# Power.net
KiCad netlist of a schematic drawn in Altium Designer
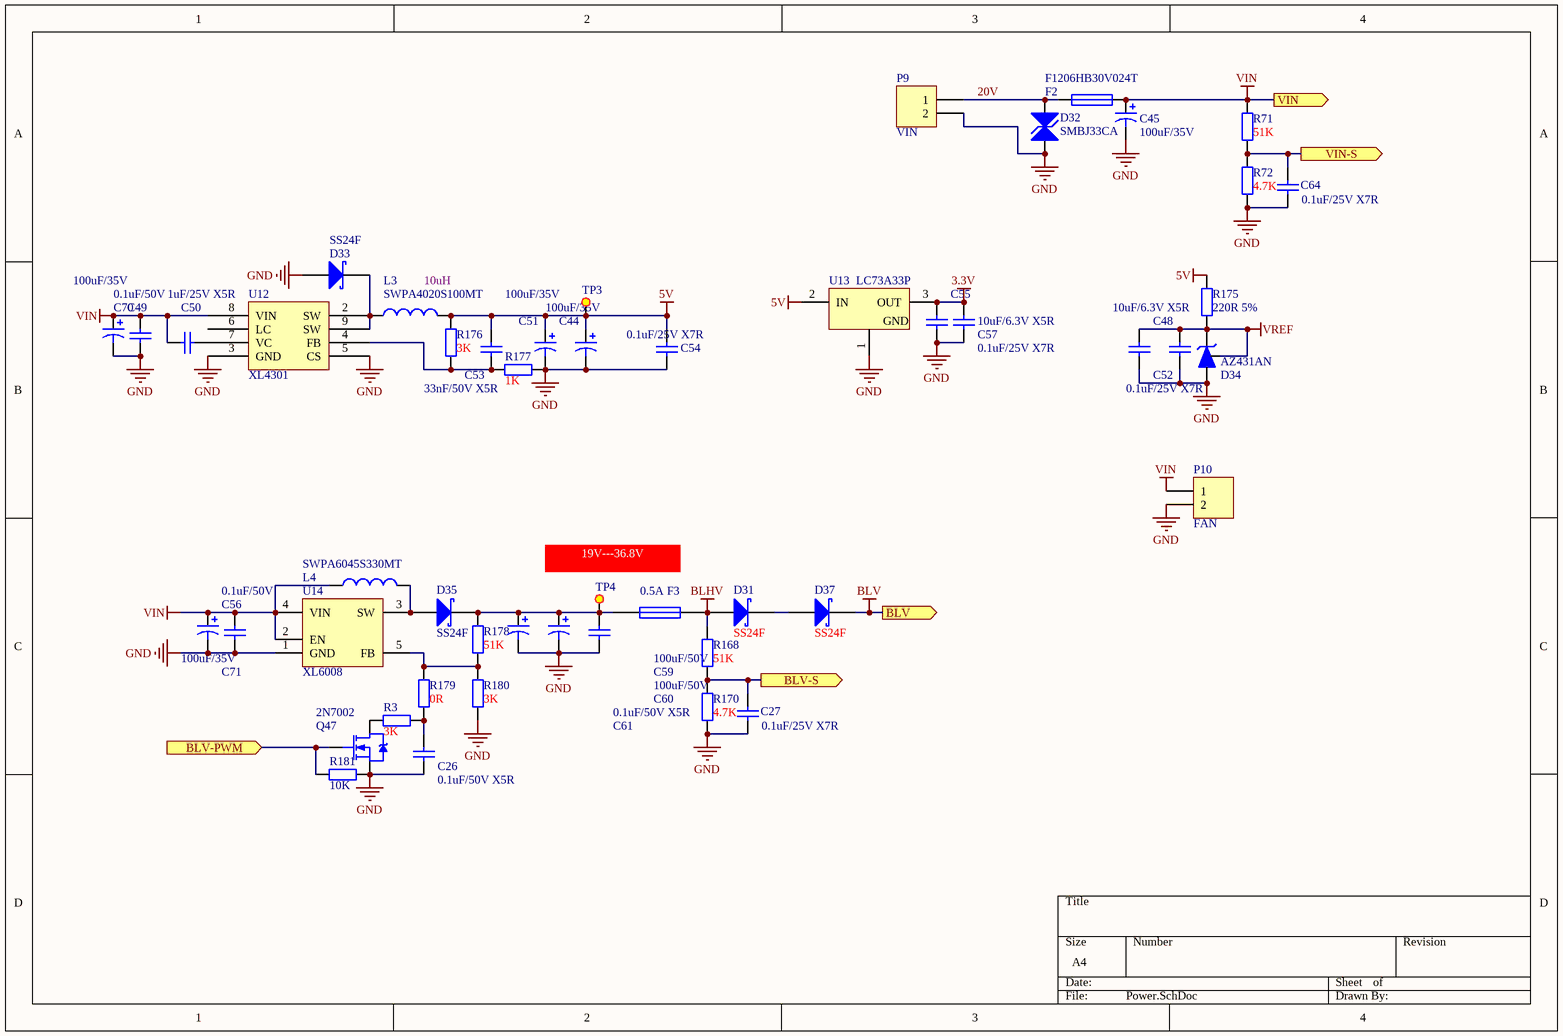
[diagram p0: Power.SchDoc]

(export (version "E")
  (design (tool "Eeschema 10.0.6"))
  (components
    (comp (ref "C26")
      (value "0.1uF/50V X5R")
      (footprint "C-0603")
      (description "Capacitor")
      (fields (field (name "PUBLISHER") "Altium Limited"))
      (libsource (lib "Miscellaneous Devices") (part "Cap"))
    )
    (comp (ref "C27")
      (value "0.1uF/25V X7R")
      (footprint "C-0603")
      (description "Capacitor")
      (fields (field (name "PUBLISHER") "Altium Limited"))
      (libsource (lib "Miscellaneous Devices") (part "Cap"))
    )
    (comp (ref "C44")
      (value "100uF/35V")
      (footprint "ToboxStd:CAP-SMD-6.3x7.7")
      (description "Polarized Capacitor (Radial)")
      (fields (field (name "PUBLISHER") "Altium Limited"))
      (libsource (lib "Miscellaneous Devices") (part "Cap Pol1"))
    )
    (comp (ref "C45")
      (value "100uF/35V")
      (footprint "ToboxStd:CAP-SMD-6.3x7.7")
      (description "Polarized Capacitor (Radial)")
      (fields (field (name "PUBLISHER") "Altium Limited"))
      (libsource (lib "Miscellaneous Devices") (part "Cap Pol1"))
    )
    (comp (ref "C48")
      (value "10uF/6.3V X5R")
      (footprint "C-0603")
      (description "Capacitor")
      (fields (field (name "PUBLISHER") "Altium Limited"))
      (libsource (lib "Miscellaneous Devices") (part "Cap"))
    )
    (comp (ref "C49")
      (value "0.1uF/50V")
      (footprint "C-0603")
      (description "Capacitor")
      (fields (field (name "PUBLISHER") "Altium Limited"))
      (libsource (lib "Miscellaneous Devices") (part "Cap"))
    )
    (comp (ref "C50")
      (value "1uF/25V X5R")
      (footprint "C-0603")
      (description "Capacitor")
      (fields (field (name "PUBLISHER") "Altium Limited"))
      (libsource (lib "Miscellaneous Devices") (part "Cap"))
    )
    (comp (ref "C51")
      (value "100uF/35V")
      (footprint "ToboxStd:CAP-SMD-6.3x7.7")
      (description "Polarized Capacitor (Radial)")
      (fields (field (name "PUBLISHER") "Altium Limited"))
      (libsource (lib "Miscellaneous Devices") (part "Cap Pol1"))
    )
    (comp (ref "C52")
      (value "0.1uF/25V X7R")
      (footprint "C-0603")
      (description "Capacitor")
      (fields (field (name "PUBLISHER") "Altium Limited"))
      (libsource (lib "Miscellaneous Devices") (part "Cap"))
    )
    (comp (ref "C53")
      (value "33nF/50V X5R")
      (footprint "C-0603")
      (description "Capacitor")
      (fields (field (name "PUBLISHER") "Altium Limited"))
      (libsource (lib "Miscellaneous Devices") (part "Cap"))
    )
    (comp (ref "C54")
      (value "0.1uF/25V X7R")
      (footprint "C-0603")
      (description "Capacitor")
      (fields (field (name "PUBLISHER") "Altium Limited"))
      (libsource (lib "Miscellaneous Devices") (part "Cap"))
    )
    (comp (ref "C55")
      (value "0.1uF/25V X7R")
      (footprint "C-0603")
      (description "Capacitor")
      (fields (field (name "PUBLISHER") "Altium Limited"))
      (libsource (lib "Miscellaneous Devices") (part "Cap"))
    )
    (comp (ref "C56")
      (value "0.1uF/50V")
      (footprint "C-0603")
      (description "Capacitor")
      (fields (field (name "PUBLISHER") "Altium Limited"))
      (libsource (lib "Miscellaneous Devices") (part "Cap"))
    )
    (comp (ref "C57")
      (value "10uF/6.3V X5R")
      (footprint "C-0603")
      (description "Capacitor")
      (fields (field (name "PUBLISHER") "Altium Limited"))
      (libsource (lib "Miscellaneous Devices") (part "Cap"))
    )
    (comp (ref "C59")
      (value "100uF/50V")
      (footprint "CAPPR-8x12")
      (description "Polarized Capacitor (Radial)")
      (fields (field (name "PUBLISHER") "Altium Limited"))
      (libsource (lib "Miscellaneous Devices") (part "Cap Pol1"))
    )
    (comp (ref "C60")
      (value "100uF/50V")
      (footprint "CAPPR-8x12")
      (description "Polarized Capacitor (Radial)")
      (fields (field (name "PUBLISHER") "Altium Limited"))
      (libsource (lib "Miscellaneous Devices") (part "Cap Pol1"))
    )
    (comp (ref "C61")
      (value "0.1uF/50V X5R")
      (footprint "C-0603")
      (description "Capacitor")
      (fields (field (name "PUBLISHER") "Altium Limited"))
      (libsource (lib "Miscellaneous Devices") (part "Cap"))
    )
    (comp (ref "C64")
      (value "0.1uF/25V X7R")
      (footprint "C-0603")
      (description "Capacitor")
      (fields (field (name "PUBLISHER") "Altium Limited"))
      (libsource (lib "Miscellaneous Devices") (part "Cap"))
    )
    (comp (ref "C70")
      (value "100uF/35V")
      (footprint "ToboxStd:CAP-SMD-6.3x7.7")
      (description "Polarized Capacitor (Radial)")
      (fields (field (name "PUBLISHER") "Altium Limited"))
      (libsource (lib "Miscellaneous Devices") (part "Cap Pol1"))
    )
    (comp (ref "C71")
      (value "100uF/35V")
      (footprint "ToboxStd:CAP-SMD-6.3x7.7")
      (description "Polarized Capacitor (Radial)")
      (fields (field (name "PUBLISHER") "Altium Limited"))
      (libsource (lib "Miscellaneous Devices") (part "Cap Pol1"))
    )
    (comp (ref "D31")
      (value "SS24F")
      (footprint "SMAF")
      (description "Schottky Diode")
      (fields
        (field (name "MANUFACTURER") "Generic Components")
        (field (name "PUBLISHER") "Altium Hobart Technology Centre")
      )
      (libsource (lib "Tobox") (part "D Schottky"))
    )
    (comp (ref "D32") (value "SMBJ33CA") (footprint "SMBJ") (libsource (lib "ToboxStd") (part "TVS-D")))
    (comp (ref "D33")
      (value "SS24F")
      (footprint "SMAF")
      (description "Schottky Diode")
      (fields
        (field (name "MANUFACTURER") "Generic Components")
        (field (name "PUBLISHER") "Altium Hobart Technology Centre")
      )
      (libsource (lib "Tobox") (part "D Schottky"))
    )
    (comp (ref "D34") (value "AZ431AN") (footprint "SOT23-3") (libsource (lib "Tobox") (part "TL431")))
    (comp (ref "D35")
      (value "SS24F")
      (footprint "SMAF")
      (description "Schottky Diode")
      (fields
        (field (name "MANUFACTURER") "Generic Components")
        (field (name "PUBLISHER") "Altium Hobart Technology Centre")
      )
      (libsource (lib "Tobox") (part "D Schottky"))
    )
    (comp (ref "D37")
      (value "SS24F")
      (footprint "SMAF")
      (description "Schottky Diode")
      (fields
        (field (name "MANUFACTURER") "Generic Components")
        (field (name "PUBLISHER") "Altium Hobart Technology Centre")
      )
      (libsource (lib "Tobox") (part "D Schottky"))
    )
    (comp (ref "F2")
      (value "F1206HB30V024T")
      (footprint "R-1206")
      (description "Fuse")
      (fields (field (name "PUBLISHER") "Altium Limited"))
      (libsource (lib "") (part "Fuse 1_1"))
    )
    (comp (ref "F3")
      (value "0.5A")
      (footprint "R-1206")
      (description "Fuse")
      (fields (field (name "PUBLISHER") "Altium Limited"))
      (libsource (lib "Miscellaneous Devices") (part "Fuse 1"))
    )
    (comp (ref "L3")
      (value "SWPA4020S100MT")
      (footprint "SWPA4020S")
      (description "Inductor")
      (fields (field (name "PUBLISHER") "Altium Limited"))
      (libsource (lib "Miscellaneous Devices") (part "Inductor"))
    )
    (comp (ref "L4")
      (value "SWPA6045S330MT")
      (footprint "SWPA6045S")
      (description "Inductor")
      (fields (field (name "PUBLISHER") "Altium Limited"))
      (libsource (lib "Miscellaneous Devices") (part "Inductor"))
    )
    (comp (ref "P9")
      (value "VIN")
      (footprint "XT30U")
      (description "Header, 2-Pin")
      (fields (field (name "PUBLISHER") "Altium Limited"))
      (libsource (lib "Miscellaneous Connectors") (part "Header 2"))
    )
    (comp (ref "P10")
      (value "FAN")
      (footprint "ToboxStd:PH-2A")
      (description "Header, 2-Pin")
      (fields (field (name "PUBLISHER") "Altium Limited"))
      (libsource (lib "") (part "Header 2_1"))
    )
    (comp (ref "Q47")
      (value "2N7002")
      (footprint "SOT23-3")
      (description "N-Channel Power MOSFET")
      (fields (field (name "PUBLISHER") "Altium Limited"))
      (libsource (lib "Miscellaneous Devices") (part "NMOS-2"))
    )
    (comp (ref "R3")
      (value "3K")
      (footprint "R-0603")
      (description "Resistor")
      (fields (field (name "PUBLISHER") "Altium Limited"))
      (libsource (lib "Miscellaneous Devices") (part "Res2"))
    )
    (comp (ref "R71")
      (value "51K")
      (footprint "R-0603")
      (description "Resistor")
      (fields (field (name "PUBLISHER") "Altium Limited"))
      (libsource (lib "Miscellaneous Devices") (part "Res2"))
    )
    (comp (ref "R72")
      (value "4.7K")
      (footprint "R-0603")
      (description "Resistor")
      (fields (field (name "PUBLISHER") "Altium Limited"))
      (libsource (lib "") (part "Res2_1"))
    )
    (comp (ref "R168")
      (value "51K")
      (footprint "R-0603")
      (description "Resistor")
      (fields (field (name "PUBLISHER") "Altium Limited"))
      (libsource (lib "Miscellaneous Devices") (part "Res2"))
    )
    (comp (ref "R170")
      (value "4.7K")
      (footprint "R-0603")
      (description "Resistor")
      (fields (field (name "PUBLISHER") "Altium Limited"))
      (libsource (lib "") (part "Res2_1"))
    )
    (comp (ref "R175")
      (value "220R 5%")
      (footprint "R-0603")
      (description "Resistor")
      (fields (field (name "PUBLISHER") "Altium Limited"))
      (libsource (lib "") (part "Res2_1"))
    )
    (comp (ref "R176")
      (value "3K")
      (footprint "R-0603")
      (description "Resistor")
      (fields (field (name "PUBLISHER") "Altium Limited"))
      (libsource (lib "Miscellaneous Devices") (part "Res2"))
    )
    (comp (ref "R177")
      (value "1K")
      (footprint "R-0603")
      (description "Resistor")
      (fields (field (name "PUBLISHER") "Altium Limited"))
      (libsource (lib "") (part "Res2_2"))
    )
    (comp (ref "R178")
      (value "51K")
      (footprint "R-0603")
      (description "Resistor")
      (fields (field (name "PUBLISHER") "Altium Limited"))
      (libsource (lib "Miscellaneous Devices") (part "Res2"))
    )
    (comp (ref "R179")
      (value "0R")
      (footprint "R-0603")
      (description "Resistor")
      (fields (field (name "PUBLISHER") "Altium Limited"))
      (libsource (lib "") (part "Res2_2"))
    )
    (comp (ref "R180")
      (value "3K")
      (footprint "R-0603")
      (description "Resistor")
      (fields (field (name "PUBLISHER") "Altium Limited"))
      (libsource (lib "") (part "Res2_1"))
    )
    (comp (ref "R181")
      (value "10K")
      (footprint "R-0603")
      (description "Resistor")
      (fields (field (name "PUBLISHER") "Altium Limited"))
      (libsource (lib "Miscellaneous Devices") (part "Res2"))
    )
    (comp (ref "TP3") (value "~") (footprint "TestPoint-1.5mm") (libsource (lib "Tobox") (part "TEST_P")))
    (comp (ref "TP4") (value "~") (footprint "TestPoint-1.5mm") (libsource (lib "Tobox") (part "TEST_P")))
    (comp (ref "U12") (value "XL4301") (footprint "SOIC8E") (libsource (lib "ToboxStd") (part "XL4301")))
    (comp (ref "U13")
      (value "LC73A33P")
      (footprint "ToboxStd:SOT89-3")
      (libsource (lib "Tobox") (part "LM7805"))
    )
    (comp (ref "U14") (value "XL6008") (footprint "TO252-5L") (libsource (lib "ToboxStd") (part "XL6008")))
  )
  (nets
    (net (code "1") (name "/20V") (class "Default")
      (node (ref "D32") (pin "1") (pinfunction "1_1") (pintype "passive"))
      (node (ref "F2") (pin "2") (pinfunction "2_2") (pintype "passive"))
      (node (ref "P9") (pin "1") (pinfunction "1_1") (pintype "passive"))
    )
    (net (code "2") (name "/BLV-PWM") (class "Default")
      (node (ref "Q47") (pin "1") (pinfunction "G_1") (pintype "passive"))
      (node (ref "R181") (pin "2") (pinfunction "2_2") (pintype "passive"))
    )
    (net (code "3") (name "/BLV-S") (class "Default")
      (node (ref "C27") (pin "2") (pinfunction "2_2") (pintype "passive"))
      (node (ref "R168") (pin "2") (pinfunction "2_2") (pintype "passive"))
      (node (ref "R170") (pin "2") (pinfunction "2_2") (pintype "passive"))
    )
    (net (code "4") (name "/VIN-S") (class "Default")
      (node (ref "C64") (pin "2") (pinfunction "2_2") (pintype "passive"))
      (node (ref "R71") (pin "2") (pinfunction "2_2") (pintype "passive"))
      (node (ref "R72") (pin "2") (pinfunction "2_2") (pintype "passive"))
    )
    (net (code "5") (name "3.3V") (class "Default")
      (node (ref "C55") (pin "2") (pinfunction "2_2") (pintype "passive"))
      (node (ref "C57") (pin "2") (pinfunction "2_2") (pintype "passive"))
      (node (ref "U13") (pin "3") (pinfunction "OUT_3") (pintype "passive"))
    )
    (net (code "6") (name "5V") (class "Default")
      (node (ref "C44") (pin "1") (pinfunction "1_1") (pintype "passive"))
      (node (ref "C51") (pin "1") (pinfunction "1_1") (pintype "passive"))
      (node (ref "C53") (pin "1") (pinfunction "1_1") (pintype "passive"))
      (node (ref "C54") (pin "1") (pinfunction "1_1") (pintype "passive"))
      (node (ref "L3") (pin "2") (pinfunction "2_2") (pintype "passive"))
      (node (ref "R175") (pin "2") (pinfunction "2_2") (pintype "passive"))
      (node (ref "R176") (pin "1") (pinfunction "1_1") (pintype "passive"))
      (node (ref "TP3") (pin "1") (pinfunction "1_1") (pintype "passive"))
      (node (ref "U13") (pin "2") (pinfunction "IN_2") (pintype "passive"))
    )
    (net (code "7") (name "BLHV") (class "Default")
      (node (ref "D31") (pin "1") (pinfunction "A_1") (pintype "passive"))
      (node (ref "F3") (pin "2") (pinfunction "2_2") (pintype "passive"))
      (node (ref "R168") (pin "1") (pinfunction "1_1") (pintype "passive"))
    )
    (net (code "8") (name "BLV") (class "Default")
      (node (ref "D37") (pin "2") (pinfunction "K_2") (pintype "passive"))
    )
    (net (code "9") (name "GND") (class "Default")
      (node (ref "C26") (pin "2") (pinfunction "2_2") (pintype "passive"))
      (node (ref "C27") (pin "1") (pinfunction "1_1") (pintype "passive"))
      (node (ref "C44") (pin "2") (pinfunction "2_2") (pintype "passive"))
      (node (ref "C45") (pin "2") (pinfunction "2_2") (pintype "passive"))
      (node (ref "C48") (pin "1") (pinfunction "1_1") (pintype "passive"))
      (node (ref "C49") (pin "1") (pinfunction "1_1") (pintype "passive"))
      (node (ref "C51") (pin "2") (pinfunction "2_2") (pintype "passive"))
      (node (ref "C52") (pin "2") (pinfunction "2_2") (pintype "passive"))
      (node (ref "C54") (pin "2") (pinfunction "2_2") (pintype "passive"))
      (node (ref "C55") (pin "1") (pinfunction "1_1") (pintype "passive"))
      (node (ref "C56") (pin "1") (pinfunction "1_1") (pintype "passive"))
      (node (ref "C57") (pin "1") (pinfunction "1_1") (pintype "passive"))
      (node (ref "C59") (pin "2") (pinfunction "2_2") (pintype "passive"))
      (node (ref "C60") (pin "2") (pinfunction "2_2") (pintype "passive"))
      (node (ref "C61") (pin "1") (pinfunction "1_1") (pintype "passive"))
      (node (ref "C64") (pin "1") (pinfunction "1_1") (pintype "passive"))
      (node (ref "C70") (pin "2") (pinfunction "2_2") (pintype "passive"))
      (node (ref "C71") (pin "2") (pinfunction "2_2") (pintype "passive"))
      (node (ref "D32") (pin "2") (pinfunction "2_2") (pintype "passive"))
      (node (ref "D33") (pin "1") (pinfunction "A_1") (pintype "passive"))
      (node (ref "D34") (pin "3") (pinfunction "A_3") (pintype "passive"))
      (node (ref "P10") (pin "2") (pinfunction "2_2") (pintype "passive"))
      (node (ref "P9") (pin "2") (pinfunction "2_2") (pintype "passive"))
      (node (ref "Q47") (pin "2") (pinfunction "D_2") (pintype "passive"))
      (node (ref "R170") (pin "1") (pinfunction "1_1") (pintype "passive"))
      (node (ref "R177") (pin "2") (pinfunction "2_2") (pintype "passive"))
      (node (ref "R180") (pin "1") (pinfunction "1_1") (pintype "passive"))
      (node (ref "R181") (pin "1") (pinfunction "1_1") (pintype "passive"))
      (node (ref "R72") (pin "1") (pinfunction "1_1") (pintype "passive"))
      (node (ref "U12") (pin "3") (pinfunction "GND_3") (pintype "passive"))
      (node (ref "U12") (pin "5") (pinfunction "CS_5") (pintype "passive"))
      (node (ref "U13") (pin "1") (pinfunction "GND_1") (pintype "passive"))
      (node (ref "U14") (pin "1") (pinfunction "GND_1") (pintype "passive"))
    )
    (net (code "10") (name "Net-(C26-Pad1)") (class "Default")
      (node (ref "C26") (pin "1") (pinfunction "1_1") (pintype "passive"))
      (node (ref "R179") (pin "1") (pinfunction "1_1") (pintype "passive"))
      (node (ref "R3") (pin "1") (pinfunction "1_1") (pintype "passive"))
    )
    (net (code "11") (name "Net-(D31-K)") (class "Default")
      (node (ref "D31") (pin "2") (pinfunction "K_2") (pintype "passive"))
      (node (ref "D37") (pin "1") (pinfunction "A_1") (pintype "passive"))
    )
    (net (code "12") (name "Net-(D33-K)") (class "Default")
      (node (ref "D33") (pin "2") (pinfunction "K_2") (pintype "passive"))
      (node (ref "L3") (pin "1") (pinfunction "1_1") (pintype "passive"))
      (node (ref "U12") (pin "2") (pinfunction "SW_2") (pintype "passive"))
      (node (ref "U12") (pin "9") (pinfunction "SW_9") (pintype "passive"))
    )
    (net (code "13") (name "Net-(D35-A)") (class "Default")
      (node (ref "D35") (pin "1") (pinfunction "A_1") (pintype "passive"))
      (node (ref "L4") (pin "2") (pinfunction "2_2") (pintype "passive"))
      (node (ref "U14") (pin "3") (pinfunction "SW_3") (pintype "passive"))
    )
    (net (code "14") (name "Net-(D35-K)") (class "Default")
      (node (ref "C59") (pin "1") (pinfunction "1_1") (pintype "passive"))
      (node (ref "C60") (pin "1") (pinfunction "1_1") (pintype "passive"))
      (node (ref "C61") (pin "2") (pinfunction "2_2") (pintype "passive"))
      (node (ref "D35") (pin "2") (pinfunction "K_2") (pintype "passive"))
      (node (ref "F3") (pin "1") (pinfunction "1_1") (pintype "passive"))
      (node (ref "R178") (pin "1") (pinfunction "1_1") (pintype "passive"))
      (node (ref "TP4") (pin "1") (pinfunction "1_1") (pintype "passive"))
    )
    (net (code "15") (name "Net-(Q47-S)") (class "Default")
      (node (ref "Q47") (pin "3") (pinfunction "S_3") (pintype "passive"))
      (node (ref "R3") (pin "2") (pinfunction "2_2") (pintype "passive"))
    )
    (net (code "16") (name "Net-(U12-FB)") (class "Default")
      (node (ref "C53") (pin "2") (pinfunction "2_2") (pintype "passive"))
      (node (ref "R176") (pin "2") (pinfunction "2_2") (pintype "passive"))
      (node (ref "R177") (pin "1") (pinfunction "1_1") (pintype "passive"))
      (node (ref "U12") (pin "4") (pinfunction "FB_4") (pintype "passive"))
    )
    (net (code "17") (name "Net-(U12-VC)") (class "Default")
      (node (ref "C50") (pin "1") (pinfunction "1_1") (pintype "passive"))
      (node (ref "U12") (pin "7") (pinfunction "VC_7") (pintype "passive"))
    )
    (net (code "18") (name "Net-(U14-FB)") (class "Default")
      (node (ref "R178") (pin "2") (pinfunction "2_2") (pintype "passive"))
      (node (ref "R179") (pin "2") (pinfunction "2_2") (pintype "passive"))
      (node (ref "R180") (pin "2") (pinfunction "2_2") (pintype "passive"))
      (node (ref "U14") (pin "5") (pinfunction "FB_5") (pintype "passive"))
    )
    (net (code "19") (name "VIN") (class "Default")
      (node (ref "C45") (pin "1") (pinfunction "1_1") (pintype "passive"))
      (node (ref "C49") (pin "2") (pinfunction "2_2") (pintype "passive"))
      (node (ref "C50") (pin "2") (pinfunction "2_2") (pintype "passive"))
      (node (ref "C56") (pin "2") (pinfunction "2_2") (pintype "passive"))
      (node (ref "C70") (pin "1") (pinfunction "1_1") (pintype "passive"))
      (node (ref "C71") (pin "1") (pinfunction "1_1") (pintype "passive"))
      (node (ref "F2") (pin "1") (pinfunction "1_1") (pintype "passive"))
      (node (ref "L4") (pin "1") (pinfunction "1_1") (pintype "passive"))
      (node (ref "P10") (pin "1") (pinfunction "1_1") (pintype "passive"))
      (node (ref "R71") (pin "1") (pinfunction "1_1") (pintype "passive"))
      (node (ref "U12") (pin "8") (pinfunction "VIN_8") (pintype "passive"))
      (node (ref "U14") (pin "2") (pinfunction "EN_2") (pintype "passive"))
      (node (ref "U14") (pin "4") (pinfunction "VIN_4") (pintype "passive"))
    )
    (net (code "20") (name "VREF") (class "Default")
      (node (ref "C48") (pin "2") (pinfunction "2_2") (pintype "passive"))
      (node (ref "C52") (pin "1") (pinfunction "1_1") (pintype "passive"))
      (node (ref "D34") (pin "1") (pinfunction "R_1") (pintype "passive"))
      (node (ref "D34") (pin "2") (pinfunction "K_2") (pintype "passive"))
      (node (ref "R175") (pin "1") (pinfunction "1_1") (pintype "passive"))
    )
    (net (code "21") (name "unconnected-(U12-LC-Pad6)") (class "Default")
      (node (ref "U12") (pin "6") (pinfunction "LC_6") (pintype "passive"))
    )
  )
)
